# Sheet1.net
KiCad netlist of a schematic drawn in Altium Designer
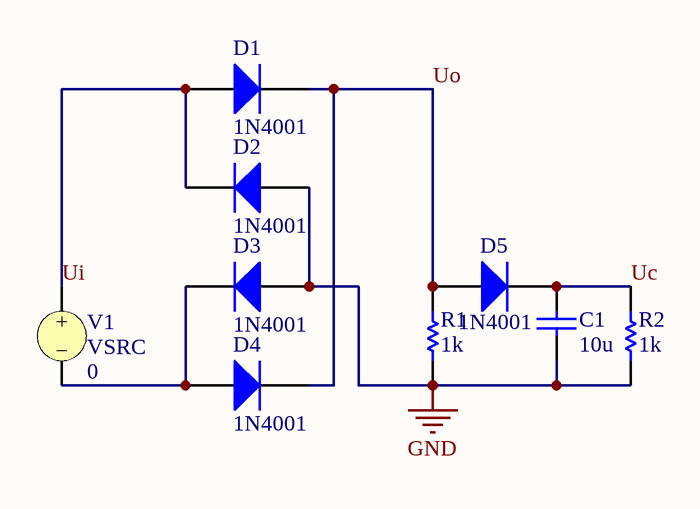
[diagram p0: Sheet1.SchDoc]

(export (version "E")
  (design (tool "Eeschema 10.0.6"))
  (components
    (comp (ref "C1")
      (value "10u")
      (description "Capacitor")
      (libsource (lib "Simulation Generic Components") (part "Capacitor"))
    )
    (comp (ref "D1")
      (value "1N4001")
      (footprint "DO-41")
      (description "1 Amp General Purpose Rectifier")
      (fields (field (name "PUBLISHER") "Altium Limited"))
      (libsource (lib "Miscellaneous Devices") (part "Diode 1N4001"))
    )
    (comp (ref "D2")
      (value "1N4001")
      (footprint "DO-41")
      (description "1 Amp General Purpose Rectifier")
      (fields (field (name "PUBLISHER") "Altium Limited"))
      (libsource (lib "Miscellaneous Devices") (part "Diode 1N4001"))
    )
    (comp (ref "D3")
      (value "1N4001")
      (footprint "DO-41")
      (description "1 Amp General Purpose Rectifier")
      (fields (field (name "PUBLISHER") "Altium Limited"))
      (libsource (lib "Miscellaneous Devices") (part "Diode 1N4001"))
    )
    (comp (ref "D4")
      (value "1N4001")
      (footprint "DO-41")
      (description "1 Amp General Purpose Rectifier")
      (fields (field (name "PUBLISHER") "Altium Limited"))
      (libsource (lib "Miscellaneous Devices") (part "Diode 1N4001"))
    )
    (comp (ref "D5")
      (value "1N4001")
      (footprint "DO-41")
      (description "1 Amp General Purpose Rectifier")
      (fields (field (name "PUBLISHER") "Altium Limited"))
      (libsource (lib "Miscellaneous Devices") (part "Diode 1N4001"))
    )
    (comp (ref "R1")
      (value "1k")
      (description "Resistor")
      (libsource (lib "Simulation Generic Components") (part "Resistor"))
    )
    (comp (ref "R2")
      (value "1k")
      (description "Resistor")
      (libsource (lib "Simulation Generic Components") (part "Resistor"))
    )
    (comp (ref "V1")
      (value "VSRC")
      (description "Voltage Source")
      (fields (field (name "DC MAGNITUDE") "0") (field (name "PUBLISHER") "Altium Limited"))
      (libsource (lib "Simulation Generic Components") (part "VSRC"))
    )
  )
  (nets
    (net (code "1") (name "/Uc") (class "Default")
      (node (ref "C1") (pin "2") (pinfunction "2_2") (pintype "passive"))
      (node (ref "D5") (pin "2") (pinfunction "K_2") (pintype "passive"))
      (node (ref "R2") (pin "1") (pinfunction "1_1") (pintype "passive"))
    )
    (net (code "2") (name "/Ui") (class "Default")
      (node (ref "D1") (pin "1") (pinfunction "A_1") (pintype "passive"))
      (node (ref "D2") (pin "2") (pinfunction "K_2") (pintype "passive"))
      (node (ref "V1") (pin "1") (pinfunction "1_1") (pintype "passive"))
    )
    (net (code "3") (name "/Uo") (class "Default")
      (node (ref "D1") (pin "2") (pinfunction "K_2") (pintype "passive"))
      (node (ref "D4") (pin "2") (pinfunction "K_2") (pintype "passive"))
      (node (ref "D5") (pin "1") (pinfunction "A_1") (pintype "passive"))
      (node (ref "R1") (pin "1") (pinfunction "1_1") (pintype "passive"))
    )
    (net (code "4") (name "GND") (class "Default")
      (node (ref "C1") (pin "1") (pinfunction "1_1") (pintype "passive"))
      (node (ref "D2") (pin "1") (pinfunction "A_1") (pintype "passive"))
      (node (ref "D3") (pin "1") (pinfunction "A_1") (pintype "passive"))
      (node (ref "R1") (pin "2") (pinfunction "2_2") (pintype "passive"))
      (node (ref "R2") (pin "2") (pinfunction "2_2") (pintype "passive"))
    )
    (net (code "5") (name "Net-(D3-K)") (class "Default")
      (node (ref "D3") (pin "2") (pinfunction "K_2") (pintype "passive"))
      (node (ref "D4") (pin "1") (pinfunction "A_1") (pintype "passive"))
      (node (ref "V1") (pin "2") (pinfunction "2_2") (pintype "passive"))
    )
  )
)
